# CC2530_PCB_Updated_Antenna_Stim_EMG.net
KiCad netlist of a schematic drawn in EAGLE
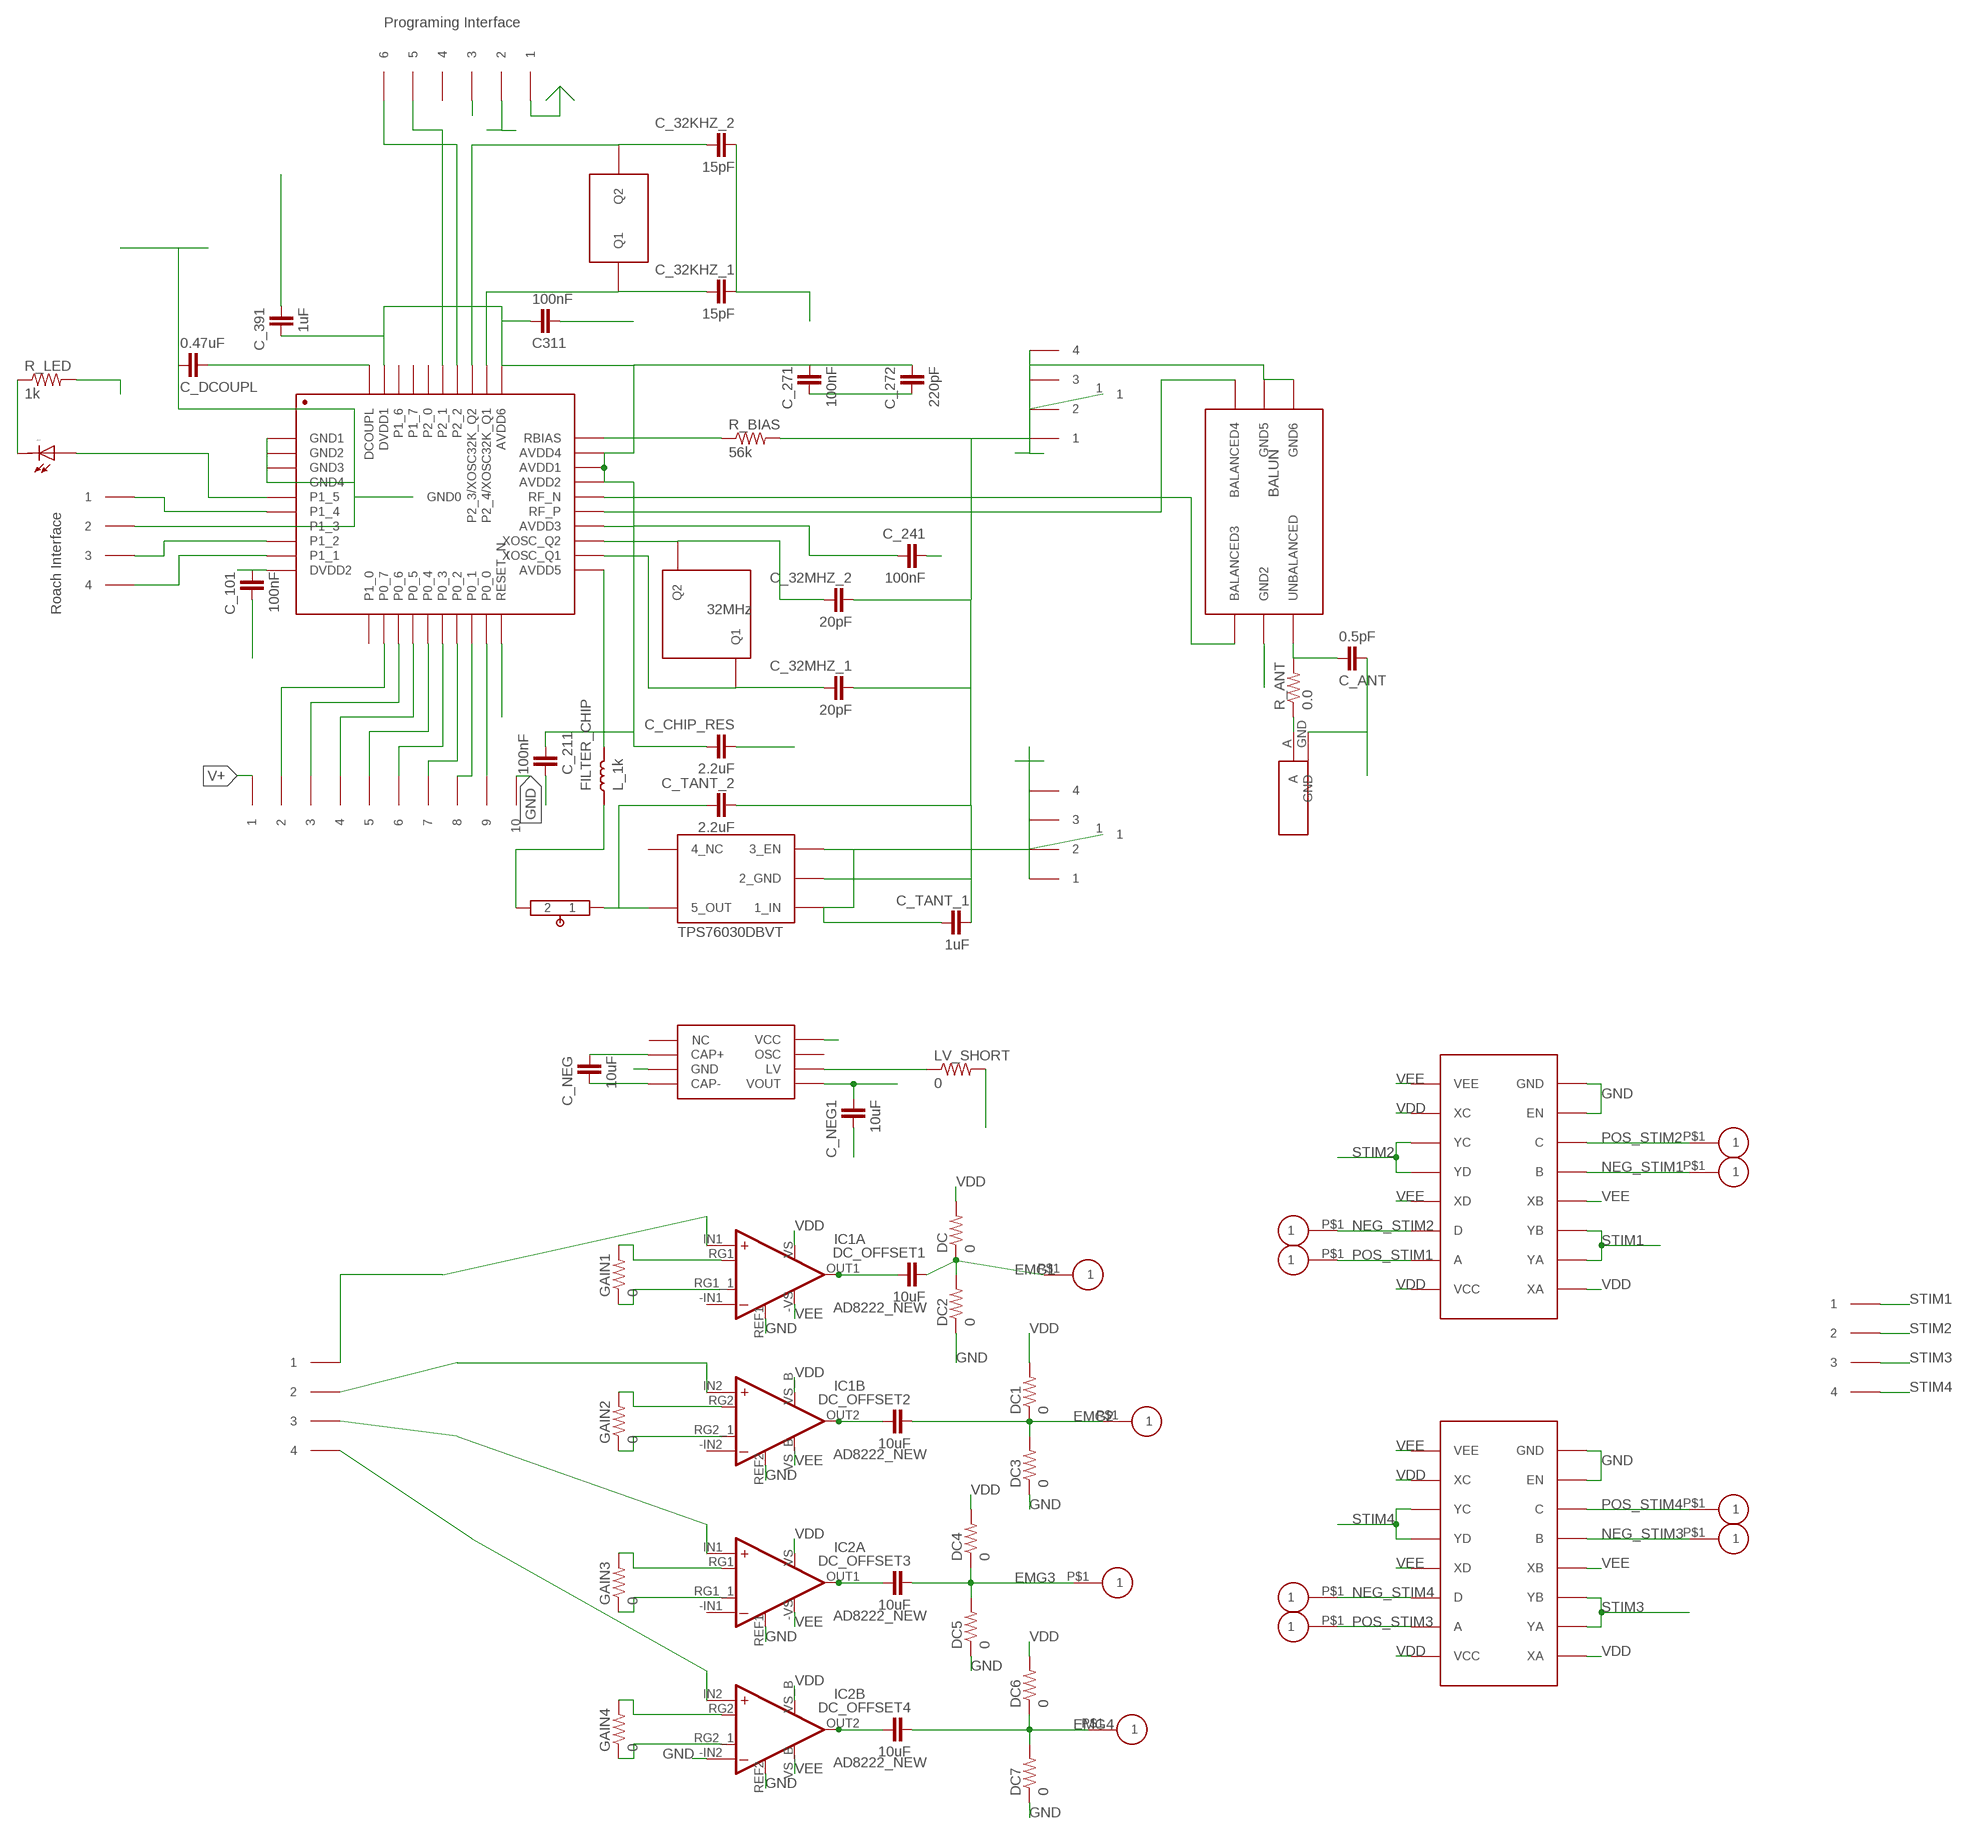
[diagram p0: schematic, sheet 1]

(export (version "E")
  (design (tool "Eeschema 10.0.6"))
  (components
    (comp (ref "32KHZ")
      (value "X32.768KHZ")
      (footprint "eagle-import:X32.768KHZ")
      (libsource (lib "eagle-import") (part "X32.768KHZ"))
    )
    (comp (ref "C311")
      (value "100nF")
      (footprint "eagle-import:0201_R_L_C")
      (libsource (lib "eagle-import") (part "0Y0X_C0201"))
    )
    (comp (ref "C_32KHZ_1")
      (value "15pF")
      (footprint "eagle-import:0201_R_L_C")
      (libsource (lib "eagle-import") (part "0Y0X_C0201"))
    )
    (comp (ref "C_32KHZ_2")
      (value "15pF")
      (footprint "eagle-import:0201_R_L_C")
      (libsource (lib "eagle-import") (part "0Y0X_C0201"))
    )
    (comp (ref "C_32MHZ_1")
      (value "20pF")
      (footprint "eagle-import:0201_R_L_C")
      (libsource (lib "eagle-import") (part "0Y0X_C0201"))
    )
    (comp (ref "C_32MHZ_2")
      (value "20pF")
      (footprint "eagle-import:0201_R_L_C")
      (libsource (lib "eagle-import") (part "0Y0X_C0201"))
    )
    (comp (ref "C_101")
      (value "100nF")
      (footprint "eagle-import:0201_R_L_C")
      (libsource (lib "eagle-import") (part "0Y0X_C0201"))
    )
    (comp (ref "C_211")
      (value "100nF")
      (footprint "eagle-import:0201_R_L_C")
      (libsource (lib "eagle-import") (part "0Y0X_C0201"))
    )
    (comp (ref "C_241")
      (value "100nF")
      (footprint "eagle-import:0201_R_L_C")
      (libsource (lib "eagle-import") (part "0Y0X_C0201"))
    )
    (comp (ref "C_271")
      (value "100nF")
      (footprint "eagle-import:0201_R_L_C")
      (libsource (lib "eagle-import") (part "0Y0X_C0201"))
    )
    (comp (ref "C_272")
      (value "220pF")
      (footprint "eagle-import:0201_R_L_C")
      (libsource (lib "eagle-import") (part "0Y0X_C0201"))
    )
    (comp (ref "C_391")
      (value "1uF")
      (footprint "eagle-import:0201_R_L_C")
      (libsource (lib "eagle-import") (part "0Y0X_C0201"))
    )
    (comp (ref "C_ANT")
      (value "0.5pF")
      (footprint "eagle-import:0201_R_L_C")
      (libsource (lib "eagle-import") (part "0Y0X_C0201"))
    )
    (comp (ref "C_CHIP_RES")
      (value "2.2uF")
      (footprint "eagle-import:0402_R_L_C")
      (libsource (lib "eagle-import") (part "0Y0X_C0402"))
    )
    (comp (ref "C_DCOUPL")
      (value "0.47uF")
      (footprint "eagle-import:0201_R_L_C")
      (libsource (lib "eagle-import") (part "0Y0X_C0201"))
    )
    (comp (ref "C_NEG")
      (value "10uF")
      (footprint "eagle-import:0402_R_L_C")
      (libsource (lib "eagle-import") (part "0Y0X_C0402"))
    )
    (comp (ref "C_NEG1")
      (value "10uF")
      (footprint "eagle-import:0402_R_L_C")
      (libsource (lib "eagle-import") (part "0Y0X_C0402"))
    )
    (comp (ref "C_TANT_1")
      (value "1uF")
      (footprint "eagle-import:0603_R_L_C")
      (libsource (lib "eagle-import") (part "0Y0X_C0603"))
    )
    (comp (ref "C_TANT_2")
      (value "2.2uF")
      (footprint "eagle-import:0603_R_L_C")
      (libsource (lib "eagle-import") (part "0Y0X_C0603"))
    )
    (comp (ref "DC")
      (value "0")
      (footprint "eagle-import:0402_R_L_C")
      (libsource (lib "eagle-import") (part "0Y0X_R0402"))
    )
    (comp (ref "DC1")
      (value "0")
      (footprint "eagle-import:0402_R_L_C")
      (libsource (lib "eagle-import") (part "0Y0X_R0402"))
    )
    (comp (ref "DC2")
      (value "0")
      (footprint "eagle-import:0402_R_L_C")
      (libsource (lib "eagle-import") (part "0Y0X_R0402"))
    )
    (comp (ref "DC3")
      (value "0")
      (footprint "eagle-import:0402_R_L_C")
      (libsource (lib "eagle-import") (part "0Y0X_R0402"))
    )
    (comp (ref "DC4")
      (value "0")
      (footprint "eagle-import:0402_R_L_C")
      (libsource (lib "eagle-import") (part "0Y0X_R0402"))
    )
    (comp (ref "DC5")
      (value "0")
      (footprint "eagle-import:0402_R_L_C")
      (libsource (lib "eagle-import") (part "0Y0X_R0402"))
    )
    (comp (ref "DC6")
      (value "0")
      (footprint "eagle-import:0402_R_L_C")
      (libsource (lib "eagle-import") (part "0Y0X_R0402"))
    )
    (comp (ref "DC7")
      (value "0")
      (footprint "eagle-import:0402_R_L_C")
      (libsource (lib "eagle-import") (part "0Y0X_R0402"))
    )
    (comp (ref "DC_OFFSET1")
      (value "10uF")
      (footprint "eagle-import:0402_R_L_C")
      (libsource (lib "eagle-import") (part "0Y0X_C0402"))
    )
    (comp (ref "DC_OFFSET2")
      (value "10uF")
      (footprint "eagle-import:0402_R_L_C")
      (libsource (lib "eagle-import") (part "0Y0X_C0402"))
    )
    (comp (ref "DC_OFFSET3")
      (value "10uF")
      (footprint "eagle-import:0402_R_L_C")
      (libsource (lib "eagle-import") (part "0Y0X_C0402"))
    )
    (comp (ref "DC_OFFSET4")
      (value "10uF")
      (footprint "eagle-import:0402_R_L_C")
      (libsource (lib "eagle-import") (part "0Y0X_C0402"))
    )
    (comp (ref "EMG1")
      (value "DBG_ELECTRODE")
      (footprint "eagle-import:DBG_ELECTRODE")
      (libsource (lib "eagle-import") (part "DBG_ELECTRODE"))
    )
    (comp (ref "FILTER_CHIP")
      (value "L_1k")
      (footprint "eagle-import:0402_R_L_C")
      (libsource (lib "eagle-import") (part "0Y0X_L0402"))
    )
    (comp (ref "GAIN1")
      (value "0")
      (footprint "eagle-import:0402_R_L_C")
      (libsource (lib "eagle-import") (part "0Y0X_R0402"))
    )
    (comp (ref "GAIN2")
      (value "0")
      (footprint "eagle-import:0402_R_L_C")
      (libsource (lib "eagle-import") (part "0Y0X_R0402"))
    )
    (comp (ref "GAIN3")
      (value "0")
      (footprint "eagle-import:0402_R_L_C")
      (libsource (lib "eagle-import") (part "0Y0X_R0402"))
    )
    (comp (ref "GAIN4")
      (value "0")
      (footprint "eagle-import:0402_R_L_C")
      (libsource (lib "eagle-import") (part "0Y0X_R0402"))
    )
    (comp (ref "GND_IN")
      (value "FFC4POS")
      (footprint "eagle-import:FFC4POS")
      (libsource (lib "eagle-import") (part "FFC4POS"))
    )
    (comp (ref "IC1")
      (value "AD8222_NEW")
      (footprint "eagle-import:QFN-16")
      (libsource (lib "eagle-import") (part "AD8222_NEW"))
    )
    (comp (ref "IC2")
      (value "AD8222_NEW")
      (footprint "eagle-import:QFN-16")
      (libsource (lib "eagle-import") (part "AD8222_NEW"))
    )
    (comp (ref "INVERTED_F-ANTENNA")
      (value "ANTENNA")
      (footprint "eagle-import:ANTENNA")
      (libsource (lib "eagle-import") (part "ANTENNA"))
    )
    (comp (ref "LED")
      (value "LED0603")
      (footprint "eagle-import:0603_R_L_C")
      (libsource (lib "eagle-import") (part "LED0603"))
    )
    (comp (ref "LV_SHORT")
      (value "0")
      (footprint "eagle-import:0402_R_L_C")
      (libsource (lib "eagle-import") (part "0Y0X_R0402"))
    )
    (comp (ref "R_ANT")
      (value "0.0")
      (footprint "eagle-import:0201_R_L_C")
      (libsource (lib "eagle-import") (part "0Y0X_R0201"))
    )
    (comp (ref "R_BIAS")
      (value "56k")
      (footprint "eagle-import:0201_R_L_C")
      (libsource (lib "eagle-import") (part "0Y0X_R0201"))
    )
    (comp (ref "R_LED")
      (value "1k")
      (footprint "eagle-import:0402_R_L_C")
      (libsource (lib "eagle-import") (part "0Y0X_R0402"))
    )
    (comp (ref "U$1")
      (value "CC2530")
      (footprint "eagle-import:CC2530")
      (libsource (lib "eagle-import") (part "CC2530"))
    )
    (comp (ref "U$2")
      (value "BALUN")
      (footprint "eagle-import:BALUN")
      (libsource (lib "eagle-import") (part "BALUN"))
    )
    (comp (ref "U$3")
      (value "X32MHZ")
      (footprint "eagle-import:X32MHZ")
      (fields (field (name "X") "32MHz"))
      (libsource (lib "eagle-import") (part "X32MHZ"))
    )
    (comp (ref "U$4")
      (value "TL7660")
      (footprint "eagle-import:S-PDSO-G8")
      (libsource (lib "eagle-import") (part "TL7660"))
    )
    (comp (ref "U$5")
      (value "MC74HC4316A")
      (footprint "eagle-import:SOIC-16-ON-SEMI")
      (libsource (lib "eagle-import") (part "MC74HC4316A"))
    )
    (comp (ref "U$6")
      (value "MC74HC4316A")
      (footprint "eagle-import:SOIC-16-ON-SEMI")
      (libsource (lib "eagle-import") (part "MC74HC4316A"))
    )
    (comp (ref "U$9")
      (value "DBG_ELECTRODE")
      (footprint "eagle-import:DBG_ELECTRODE")
      (libsource (lib "eagle-import") (part "DBG_ELECTRODE"))
    )
    (comp (ref "U$10")
      (value "REGULATOR")
      (footprint "eagle-import:REGULATOR")
      (libsource (lib "eagle-import") (part "REGULATOR"))
    )
    (comp (ref "U$11")
      (value "DBG_ELECTRODE")
      (footprint "eagle-import:DBG_ELECTRODE")
      (libsource (lib "eagle-import") (part "DBG_ELECTRODE"))
    )
    (comp (ref "U$12")
      (value "DBG_ELECTRODE")
      (footprint "eagle-import:DBG_ELECTRODE")
      (libsource (lib "eagle-import") (part "DBG_ELECTRODE"))
    )
    (comp (ref "U$13")
      (value "FFC4POS")
      (footprint "eagle-import:FFC4POS")
      (libsource (lib "eagle-import") (part "FFC4POS"))
    )
    (comp (ref "U$14")
      (value "DBG_ELECTRODE")
      (footprint "eagle-import:DBG_ELECTRODE")
      (libsource (lib "eagle-import") (part "DBG_ELECTRODE"))
    )
    (comp (ref "U$15")
      (value "FFC10POS")
      (footprint "eagle-import:FFC10POS")
      (libsource (lib "eagle-import") (part "FFC10POS"))
    )
    (comp (ref "U$16")
      (value "DBG_ELECTRODE")
      (footprint "eagle-import:DBG_ELECTRODE")
      (libsource (lib "eagle-import") (part "DBG_ELECTRODE"))
    )
    (comp (ref "U$17")
      (value "FFC6POS")
      (footprint "eagle-import:FFC6POS")
      (libsource (lib "eagle-import") (part "FFC6POS"))
    )
    (comp (ref "U$18")
      (value "SWITCH_MANUAL")
      (footprint "eagle-import:SWITCH_MANUAL")
      (libsource (lib "eagle-import") (part "SWITCH_MANUAL"))
    )
    (comp (ref "U$19")
      (value "DBG_ELECTRODE")
      (footprint "eagle-import:DBG_ELECTRODE")
      (libsource (lib "eagle-import") (part "DBG_ELECTRODE"))
    )
    (comp (ref "U$22")
      (value "DBG_ELECTRODE")
      (footprint "eagle-import:DBG_ELECTRODE")
      (libsource (lib "eagle-import") (part "DBG_ELECTRODE"))
    )
    (comp (ref "U$23")
      (value "DBG_ELECTRODE")
      (footprint "eagle-import:DBG_ELECTRODE")
      (libsource (lib "eagle-import") (part "DBG_ELECTRODE"))
    )
    (comp (ref "U$24")
      (value "FFC4POS")
      (footprint "eagle-import:FFC4POS")
      (libsource (lib "eagle-import") (part "FFC4POS"))
    )
    (comp (ref "U$25")
      (value "DBG_ELECTRODE")
      (footprint "eagle-import:DBG_ELECTRODE")
      (libsource (lib "eagle-import") (part "DBG_ELECTRODE"))
    )
    (comp (ref "U$26")
      (value "DBG_ELECTRODE")
      (footprint "eagle-import:DBG_ELECTRODE")
      (libsource (lib "eagle-import") (part "DBG_ELECTRODE"))
    )
    (comp (ref "U$27")
      (value "DBG_ELECTRODE")
      (footprint "eagle-import:DBG_ELECTRODE")
      (libsource (lib "eagle-import") (part "DBG_ELECTRODE"))
    )
    (comp (ref "U$28")
      (value "FFC4POS")
      (footprint "eagle-import:FFC4POS")
      (libsource (lib "eagle-import") (part "FFC4POS"))
    )
    (comp (ref "V+_IN")
      (value "FFC4POS")
      (footprint "eagle-import:FFC4POS")
      (libsource (lib "eagle-import") (part "FFC4POS"))
    )
    (comp (ref "WIRE+")
      (value "DRILL_CONNECT")
      (footprint "eagle-import:DRILL_CONNECT")
      (libsource (lib "eagle-import") (part "DRILL_CONNECT"))
    )
    (comp (ref "WIRE-")
      (value "DRILL_CONNECT")
      (footprint "eagle-import:DRILL_CONNECT")
      (libsource (lib "eagle-import") (part "DRILL_CONNECT"))
    )
  )
  (nets
    (net (code "1") (name "/EMG1") (class "Default")
      (node (ref "DC") (pin "1") (pinfunction "1_1") (pintype "passive"))
      (node (ref "DC2") (pin "2") (pinfunction "2_2") (pintype "passive"))
      (node (ref "DC_OFFSET1") (pin "2") (pinfunction "2_2") (pintype "passive"))
      (node (ref "EMG1") (pin "P$1") (pinfunction "1_P$1") (pintype "bidirectional"))
    )
    (net (code "2") (name "/EMG2") (class "Default")
      (node (ref "DC1") (pin "1") (pinfunction "1_1") (pintype "passive"))
      (node (ref "DC3") (pin "2") (pinfunction "2_2") (pintype "passive"))
      (node (ref "DC_OFFSET2") (pin "2") (pinfunction "2_2") (pintype "passive"))
      (node (ref "U$25") (pin "P$1") (pinfunction "1_P$1") (pintype "bidirectional"))
    )
    (net (code "3") (name "/EMG3") (class "Default")
      (node (ref "DC4") (pin "1") (pinfunction "1_1") (pintype "passive"))
      (node (ref "DC5") (pin "2") (pinfunction "2_2") (pintype "passive"))
      (node (ref "DC_OFFSET3") (pin "2") (pinfunction "2_2") (pintype "passive"))
      (node (ref "U$26") (pin "P$1") (pinfunction "1_P$1") (pintype "bidirectional"))
    )
    (net (code "4") (name "/EMG4") (class "Default")
      (node (ref "DC6") (pin "1") (pinfunction "1_1") (pintype "passive"))
      (node (ref "DC7") (pin "2") (pinfunction "2_2") (pintype "passive"))
      (node (ref "DC_OFFSET4") (pin "2") (pinfunction "2_2") (pintype "passive"))
      (node (ref "U$27") (pin "P$1") (pinfunction "1_P$1") (pintype "bidirectional"))
    )
    (net (code "5") (name "/NC") (class "Default")
      (node (ref "U$4") (pin "1") (pinfunction "NC_1") (pintype "power_in"))
    )
    (net (code "6") (name "/NEG_STIM1") (class "Default")
      (node (ref "U$14") (pin "P$1") (pinfunction "1_P$1") (pintype "bidirectional"))
      (node (ref "U$5") (pin "5") (pinfunction "B_5") (pintype "input"))
    )
    (net (code "7") (name "/NEG_STIM2") (class "Default")
      (node (ref "U$5") (pin "14") (pinfunction "D_14") (pintype "input"))
      (node (ref "U$9") (pin "P$1") (pinfunction "1_P$1") (pintype "bidirectional"))
    )
    (net (code "8") (name "/NEG_STIM3") (class "Default")
      (node (ref "U$19") (pin "P$1") (pinfunction "1_P$1") (pintype "bidirectional"))
      (node (ref "U$6") (pin "5") (pinfunction "B_5") (pintype "input"))
    )
    (net (code "9") (name "/NEG_STIM4") (class "Default")
      (node (ref "U$22") (pin "P$1") (pinfunction "1_P$1") (pintype "bidirectional"))
      (node (ref "U$6") (pin "14") (pinfunction "D_14") (pintype "input"))
    )
    (net (code "10") (name "/OSC") (class "Default")
      (node (ref "U$4") (pin "7") (pinfunction "OSC_7") (pintype "power_in"))
    )
    (net (code "11") (name "/POS_STIM1") (class "Default")
      (node (ref "U$11") (pin "P$1") (pinfunction "1_P$1") (pintype "bidirectional"))
      (node (ref "U$5") (pin "15") (pinfunction "A_15") (pintype "input"))
    )
    (net (code "12") (name "/POS_STIM2") (class "Default")
      (node (ref "U$12") (pin "P$1") (pinfunction "1_P$1") (pintype "bidirectional"))
      (node (ref "U$5") (pin "6") (pinfunction "C_6") (pintype "input"))
    )
    (net (code "13") (name "/POS_STIM3") (class "Default")
      (node (ref "U$23") (pin "P$1") (pinfunction "1_P$1") (pintype "bidirectional"))
      (node (ref "U$6") (pin "15") (pinfunction "A_15") (pintype "input"))
    )
    (net (code "14") (name "/POS_STIM4") (class "Default")
      (node (ref "U$16") (pin "P$1") (pinfunction "1_P$1") (pintype "bidirectional"))
      (node (ref "U$6") (pin "6") (pinfunction "C_6") (pintype "input"))
    )
    (net (code "15") (name "/RESET") (class "Default")
      (node (ref "U$1") (pin "RESET_N") (pinfunction "RESET_N_RESET_N") (pintype "input"))
      (node (ref "U$17") (pin "3") (pinfunction "3_3") (pintype "bidirectional"))
    )
    (net (code "16") (name "/STIM1") (class "Default")
      (node (ref "U$28") (pin "1") (pinfunction "1_1") (pintype "bidirectional"))
      (node (ref "U$5") (pin "2") (pinfunction "YA_2") (pintype "output"))
      (node (ref "U$5") (pin "3") (pinfunction "YB_3") (pintype "output"))
    )
    (net (code "17") (name "/STIM2") (class "Default")
      (node (ref "U$28") (pin "2") (pinfunction "2_2") (pintype "bidirectional"))
      (node (ref "U$5") (pin "11") (pinfunction "YC_11") (pintype "output"))
      (node (ref "U$5") (pin "12") (pinfunction "YD_12") (pintype "output"))
    )
    (net (code "18") (name "/STIM3") (class "Default")
      (node (ref "U$28") (pin "3") (pinfunction "3_3") (pintype "bidirectional"))
      (node (ref "U$6") (pin "2") (pinfunction "YA_2") (pintype "output"))
      (node (ref "U$6") (pin "3") (pinfunction "YB_3") (pintype "output"))
    )
    (net (code "19") (name "/STIM4") (class "Default")
      (node (ref "U$28") (pin "4") (pinfunction "4_4") (pintype "bidirectional"))
      (node (ref "U$6") (pin "11") (pinfunction "YC_11") (pintype "output"))
      (node (ref "U$6") (pin "12") (pinfunction "YD_12") (pintype "output"))
    )
    (net (code "20") (name "/VDD") (class "Default")
      (node (ref "C311") (pin "2") (pinfunction "2_2") (pintype "passive"))
      (node (ref "C_101") (pin "2") (pinfunction "2_2") (pintype "passive"))
      (node (ref "C_211") (pin "1") (pinfunction "1_1") (pintype "passive"))
      (node (ref "C_241") (pin "1") (pinfunction "1_1") (pintype "passive"))
      (node (ref "C_271") (pin "2") (pinfunction "2_2") (pintype "passive"))
      (node (ref "C_272") (pin "2") (pinfunction "2_2") (pintype "passive"))
      (node (ref "C_391") (pin "1") (pinfunction "1_1") (pintype "passive"))
      (node (ref "C_CHIP_RES") (pin "1") (pinfunction "1_1") (pintype "passive"))
      (node (ref "DC") (pin "2") (pinfunction "2_2") (pintype "passive"))
      (node (ref "DC1") (pin "2") (pinfunction "2_2") (pintype "passive"))
      (node (ref "DC4") (pin "2") (pinfunction "2_2") (pintype "passive"))
      (node (ref "DC6") (pin "2") (pinfunction "2_2") (pintype "passive"))
      (node (ref "FILTER_CHIP") (pin "2") (pinfunction "2_2") (pintype "bidirectional"))
      (node (ref "IC1") (pin "VS") (pinfunction "V+_VS") (pintype "power_in"))
      (node (ref "IC1") (pin "VS_B") (pinfunction "V+_VS_B") (pintype "power_in"))
      (node (ref "IC2") (pin "VS") (pinfunction "V+_VS") (pintype "power_in"))
      (node (ref "IC2") (pin "VS_B") (pinfunction "V+_VS_B") (pintype "power_in"))
      (node (ref "U$1") (pin "AVDD1") (pinfunction "AVDD1_AVDD1") (pintype "power_in"))
      (node (ref "U$1") (pin "AVDD2") (pinfunction "AVDD2_AVDD2") (pintype "power_in"))
      (node (ref "U$1") (pin "AVDD3") (pinfunction "AVDD3_AVDD3") (pintype "power_in"))
      (node (ref "U$1") (pin "AVDD4") (pinfunction "AVDD4_AVDD4") (pintype "power_in"))
      (node (ref "U$1") (pin "AVDD5") (pinfunction "AVDD5_AVDD5") (pintype "power_in"))
      (node (ref "U$1") (pin "AVDD6") (pinfunction "AVDD6_AVDD6") (pintype "power_in"))
      (node (ref "U$1") (pin "DVDD1") (pinfunction "DVDD1_DVDD1") (pintype "power_in"))
      (node (ref "U$1") (pin "DVDD2") (pinfunction "DVDD2_DVDD2") (pintype "power_in"))
      (node (ref "U$17") (pin "1") (pinfunction "1_1") (pintype "bidirectional"))
      (node (ref "U$4") (pin "8") (pinfunction "VCC_8") (pintype "power_in"))
      (node (ref "U$5") (pin "1") (pinfunction "XA_1") (pintype "input"))
      (node (ref "U$5") (pin "10") (pinfunction "XC_10") (pintype "input"))
      (node (ref "U$5") (pin "16") (pinfunction "VCC_16") (pintype "power_in"))
      (node (ref "U$6") (pin "1") (pinfunction "XA_1") (pintype "input"))
      (node (ref "U$6") (pin "10") (pinfunction "XC_10") (pintype "input"))
      (node (ref "U$6") (pin "16") (pinfunction "VCC_16") (pintype "power_in"))
    )
    (net (code "21") (name "/VEE") (class "Default")
      (node (ref "C_NEG1") (pin "2") (pinfunction "2_2") (pintype "passive"))
      (node (ref "IC1") (pin "-VS") (pinfunction "V-_-VS") (pintype "power_in"))
      (node (ref "IC1") (pin "-VS_B") (pinfunction "V-_-VS_B") (pintype "power_in"))
      (node (ref "IC2") (pin "-VS") (pinfunction "V-_-VS") (pintype "power_in"))
      (node (ref "IC2") (pin "-VS_B") (pinfunction "V-_-VS_B") (pintype "power_in"))
      (node (ref "U$4") (pin "5") (pinfunction "VOUT_5") (pintype "power_in"))
      (node (ref "U$5") (pin "13") (pinfunction "XD_13") (pintype "input"))
      (node (ref "U$5") (pin "4") (pinfunction "XB_4") (pintype "input"))
      (node (ref "U$5") (pin "9") (pinfunction "VEE_9") (pintype "power_in"))
      (node (ref "U$6") (pin "13") (pinfunction "XD_13") (pintype "input"))
      (node (ref "U$6") (pin "4") (pinfunction "XB_4") (pintype "input"))
      (node (ref "U$6") (pin "9") (pinfunction "VEE_9") (pintype "power_in"))
    )
    (net (code "22") (name "GND") (class "Default")
      (node (ref "C311") (pin "1") (pinfunction "1_1") (pintype "passive"))
      (node (ref "C_101") (pin "1") (pinfunction "1_1") (pintype "passive"))
      (node (ref "C_211") (pin "2") (pinfunction "2_2") (pintype "passive"))
      (node (ref "C_241") (pin "2") (pinfunction "2_2") (pintype "passive"))
      (node (ref "C_271") (pin "1") (pinfunction "1_1") (pintype "passive"))
      (node (ref "C_272") (pin "1") (pinfunction "1_1") (pintype "passive"))
      (node (ref "C_32KHZ_1") (pin "2") (pinfunction "2_2") (pintype "passive"))
      (node (ref "C_32KHZ_2") (pin "2") (pinfunction "2_2") (pintype "passive"))
      (node (ref "C_32MHZ_1") (pin "2") (pinfunction "2_2") (pintype "passive"))
      (node (ref "C_32MHZ_2") (pin "2") (pinfunction "2_2") (pintype "passive"))
      (node (ref "C_391") (pin "2") (pinfunction "2_2") (pintype "passive"))
      (node (ref "C_ANT") (pin "1") (pinfunction "1_1") (pintype "passive"))
      (node (ref "C_CHIP_RES") (pin "2") (pinfunction "2_2") (pintype "passive"))
      (node (ref "C_DCOUPL") (pin "2") (pinfunction "2_2") (pintype "passive"))
      (node (ref "C_NEG1") (pin "1") (pinfunction "1_1") (pintype "passive"))
      (node (ref "C_TANT_1") (pin "2") (pinfunction "2_2") (pintype "passive"))
      (node (ref "C_TANT_2") (pin "2") (pinfunction "2_2") (pintype "passive"))
      (node (ref "DC2") (pin "1") (pinfunction "1_1") (pintype "passive"))
      (node (ref "DC3") (pin "1") (pinfunction "1_1") (pintype "passive"))
      (node (ref "DC5") (pin "1") (pinfunction "1_1") (pintype "passive"))
      (node (ref "DC7") (pin "1") (pinfunction "1_1") (pintype "passive"))
      (node (ref "GND_IN") (pin "1") (pinfunction "1_1") (pintype "bidirectional"))
      (node (ref "GND_IN") (pin "2") (pinfunction "2_2") (pintype "bidirectional"))
      (node (ref "GND_IN") (pin "3") (pinfunction "3_3") (pintype "bidirectional"))
      (node (ref "GND_IN") (pin "4") (pinfunction "4_4") (pintype "bidirectional"))
      (node (ref "IC1") (pin "REF1") (pinfunction "REF_REF1") (pintype "input"))
      (node (ref "IC1") (pin "REF2") (pinfunction "REF_REF2") (pintype "input"))
      (node (ref "IC2") (pin "-IN2") (pinfunction "-IN_-IN2") (pintype "input"))
      (node (ref "IC2") (pin "REF1") (pinfunction "REF_REF1") (pintype "input"))
      (node (ref "IC2") (pin "REF2") (pinfunction "REF_REF2") (pintype "input"))
      (node (ref "INVERTED_F-ANTENNA") (pin "GND") (pinfunction "GND_GND") (pintype "power_in"))
      (node (ref "LV_SHORT") (pin "2") (pinfunction "2_2") (pintype "passive"))
      (node (ref "R_BIAS") (pin "2") (pinfunction "2_2") (pintype "passive"))
      (node (ref "R_LED") (pin "2") (pinfunction "2_2") (pintype "passive"))
      (node (ref "U$1") (pin "GND0") (pinfunction "GND0_GND0") (pintype "power_in"))
      (node (ref "U$1") (pin "GND001") (pinfunction "GND0_GND001") (pintype "power_in"))
      (node (ref "U$1") (pin "GND002") (pinfunction "GND0_GND002") (pintype "power_in"))
      (node (ref "U$1") (pin "GND003") (pinfunction "GND0_GND003") (pintype "power_in"))
      (node (ref "U$1") (pin "GND004") (pinfunction "GND0_GND004") (pintype "power_in"))
      (node (ref "U$1") (pin "GND005") (pinfunction "GND0_GND005") (pintype "power_in"))
      (node (ref "U$1") (pin "GND006") (pinfunction "GND0_GND006") (pintype "power_in"))
      (node (ref "U$1") (pin "GND007") (pinfunction "GND0_GND007") (pintype "power_in"))
      (node (ref "U$1") (pin "GND008") (pinfunction "GND0_GND008") (pintype "power_in"))
      (node (ref "U$1") (pin "GND009") (pinfunction "GND0_GND009") (pintype "power_in"))
      (node (ref "U$1") (pin "GND010") (pinfunction "GND0_GND010") (pintype "power_in"))
      (node (ref "U$1") (pin "GND011") (pinfunction "GND0_GND011") (pintype "power_in"))
      (node (ref "U$1") (pin "GND012") (pinfunction "GND0_GND012") (pintype "power_in"))
      (node (ref "U$1") (pin "GND013") (pinfunction "GND0_GND013") (pintype "power_in"))
      (node (ref "U$1") (pin "GND014") (pinfunction "GND0_GND014") (pintype "power_in"))
      (node (ref "U$1") (pin "GND015") (pinfunction "GND0_GND015") (pintype "power_in"))
      (node (ref "U$1") (pin "GND016") (pinfunction "GND0_GND016") (pintype "power_in"))
      (node (ref "U$1") (pin "GND1") (pinfunction "GND1_GND1") (pintype "power_in"))
      (node (ref "U$1") (pin "GND2") (pinfunction "GND2_GND2") (pintype "power_in"))
      (node (ref "U$1") (pin "GND3") (pinfunction "GND3_GND3") (pintype "power_in"))
      (node (ref "U$1") (pin "GND4") (pinfunction "GND4_GND4") (pintype "power_in"))
      (node (ref "U$1") (pin "P1_3") (pinfunction "P1_3_P1_3") (pintype "bidirectional"))
      (node (ref "U$10") (pin "2") (pinfunction "2_GND_2") (pintype "power_in"))
      (node (ref "U$13") (pin "2") (pinfunction "2_2") (pintype "bidirectional"))
      (node (ref "U$15") (pin "10") (pinfunction "10_10") (pintype "bidirectional"))
      (node (ref "U$17") (pin "2") (pinfunction "2_2") (pintype "bidirectional"))
      (node (ref "U$2") (pin "GND2") (pinfunction "GND2_GND2") (pintype "power_in"))
      (node (ref "U$2") (pin "GND5") (pinfunction "GND5_GND5") (pintype "power_in"))
      (node (ref "U$2") (pin "GND6") (pinfunction "GND6_GND6") (pintype "power_in"))
      (node (ref "U$4") (pin "3") (pinfunction "GND_3") (pintype "power_in"))
      (node (ref "U$5") (pin "7") (pinfunction "EN_7") (pintype "input"))
      (node (ref "U$5") (pin "8") (pinfunction "GND_8") (pintype "power_in"))
      (node (ref "U$6") (pin "7") (pinfunction "EN_7") (pintype "input"))
      (node (ref "U$6") (pin "8") (pinfunction "GND_8") (pintype "power_in"))
      (node (ref "WIRE-") (pin "1") (pinfunction "1_1") (pintype "bidirectional"))
    )
    (net (code "23") (name "Net-(32KHZ-PadQ1)") (class "Default")
      (node (ref "32KHZ") (pin "Q1") (pinfunction "Q1_Q1") (pintype "bidirectional"))
      (node (ref "C_32KHZ_1") (pin "1") (pinfunction "1_1") (pintype "passive"))
      (node (ref "U$1") (pin "P2_4/XOSC32K_Q1") (pinfunction "P2_4/XOSC32K_Q1_P2_4/XOSC32K_Q1") (pintype "bidirectional"))
    )
    (net (code "24") (name "Net-(32KHZ-PadQ2)") (class "Default")
      (node (ref "32KHZ") (pin "Q2") (pinfunction "Q2_Q2") (pintype "bidirectional"))
      (node (ref "C_32KHZ_2") (pin "1") (pinfunction "1_1") (pintype "passive"))
      (node (ref "U$1") (pin "P2_3/XOSC32K_Q2") (pinfunction "P2_3/XOSC32K_Q2_P2_3/XOSC32K_Q2") (pintype "bidirectional"))
    )
    (net (code "25") (name "Net-(C_32MHZ_1-Pad1)") (class "Default")
      (node (ref "C_32MHZ_1") (pin "1") (pinfunction "1_1") (pintype "passive"))
      (node (ref "U$1") (pin "XOSC_Q1") (pinfunction "XOSC_Q1_XOSC_Q1") (pintype "bidirectional"))
      (node (ref "U$3") (pin "Q1") (pinfunction "Q1_Q1") (pintype "bidirectional"))
    )
    (net (code "26") (name "Net-(C_32MHZ_2-Pad1)") (class "Default")
      (node (ref "C_32MHZ_2") (pin "1") (pinfunction "1_1") (pintype "passive"))
      (node (ref "U$1") (pin "XOSC_Q2") (pinfunction "XOSC_Q2_XOSC_Q2") (pintype "bidirectional"))
      (node (ref "U$3") (pin "Q2") (pinfunction "Q2_Q2") (pintype "bidirectional"))
    )
    (net (code "27") (name "Net-(C_ANT-Pad2)") (class "Default")
      (node (ref "C_ANT") (pin "2") (pinfunction "2_2") (pintype "passive"))
      (node (ref "R_ANT") (pin "2") (pinfunction "2_2") (pintype "passive"))
      (node (ref "U$2") (pin "UNBALANCED") (pinfunction "UNBALANCED_UNBALANCED") (pintype "bidirectional"))
    )
    (net (code "28") (name "Net-(C_DCOUPL-Pad1)") (class "Default")
      (node (ref "C_DCOUPL") (pin "1") (pinfunction "1_1") (pintype "passive"))
      (node (ref "U$1") (pin "DCOUPL") (pinfunction "DCOUPL_DCOUPL") (pintype "power_in"))
    )
    (net (code "29") (name "Net-(FILTER_CHIP-Pad1)") (class "Default")
      (node (ref "FILTER_CHIP") (pin "1") (pinfunction "1_1") (pintype "bidirectional"))
      (node (ref "U$18") (pin "2") (pinfunction "2_2") (pintype "bidirectional"))
    )
    (net (code "30") (name "Net-(GAIN1-Pad1)") (class "Default")
      (node (ref "GAIN1") (pin "1") (pinfunction "1_1") (pintype "passive"))
      (node (ref "IC1") (pin "RG1_1") (pinfunction "RG1_1_RG1_1") (pintype "input"))
    )
    (net (code "31") (name "Net-(GAIN1-Pad2)") (class "Default")
      (node (ref "GAIN1") (pin "2") (pinfunction "2_2") (pintype "passive"))
      (node (ref "IC1") (pin "RG1") (pinfunction "RG1_RG1") (pintype "input"))
    )
    (net (code "32") (name "Net-(GAIN3-Pad1)") (class "Default")
      (node (ref "GAIN3") (pin "1") (pinfunction "1_1") (pintype "passive"))
      (node (ref "IC2") (pin "RG1_1") (pinfunction "RG1_1_RG1_1") (pintype "input"))
    )
    (net (code "33") (name "Net-(GAIN3-Pad2)") (class "Default")
      (node (ref "GAIN3") (pin "2") (pinfunction "2_2") (pintype "passive"))
      (node (ref "IC2") (pin "RG1") (pinfunction "RG1_RG1") (pintype "input"))
    )
    (net (code "34") (name "Net-(IC1A-+IN)") (class "Default")
      (node (ref "IC1") (pin "IN1") (pinfunction "+IN_IN1") (pintype "input"))
      (node (ref "U$24") (pin "1") (pinfunction "1_1") (pintype "bidirectional"))
    )
    (net (code "35") (name "Net-(IC1A-OUT)") (class "Default")
      (node (ref "DC_OFFSET1") (pin "1") (pinfunction "1_1") (pintype "passive"))
      (node (ref "IC1") (pin "OUT1") (pinfunction "OUT_OUT1") (pintype "input"))
    )
    (net (code "36") (name "Net-(IC1B-+IN)") (class "Default")
      (node (ref "IC1") (pin "IN2") (pinfunction "+IN_IN2") (pintype "input"))
      (node (ref "U$24") (pin "2") (pinfunction "2_2") (pintype "bidirectional"))
    )
    (net (code "37") (name "Net-(IC1B-OUT)") (class "Default")
      (node (ref "DC_OFFSET2") (pin "1") (pinfunction "1_1") (pintype "passive"))
      (node (ref "IC1") (pin "OUT2") (pinfunction "OUT_OUT2") (pintype "input"))
    )
    (net (code "38") (name "Net-(IC1B-RG1)") (class "Default")
      (node (ref "GAIN2") (pin "2") (pinfunction "2_2") (pintype "passive"))
      (node (ref "IC1") (pin "RG2") (pinfunction "RG1_RG2") (pintype "input"))
    )
    (net (code "39") (name "Net-(IC1B-RG1_1)") (class "Default")
      (node (ref "GAIN2") (pin "1") (pinfunction "1_1") (pintype "passive"))
      (node (ref "IC1") (pin "RG2_1") (pinfunction "RG1_1_RG2_1") (pintype "input"))
    )
    (net (code "40") (name "Net-(IC2A-+IN)") (class "Default")
      (node (ref "IC2") (pin "IN1") (pinfunction "+IN_IN1") (pintype "input"))
      (node (ref "U$24") (pin "3") (pinfunction "3_3") (pintype "bidirectional"))
    )
    (net (code "41") (name "Net-(IC2A-OUT)") (class "Default")
      (node (ref "DC_OFFSET3") (pin "1") (pinfunction "1_1") (pintype "passive"))
      (node (ref "IC2") (pin "OUT1") (pinfunction "OUT_OUT1") (pintype "input"))
    )
    (net (code "42") (name "Net-(IC2B-+IN)") (class "Default")
      (node (ref "IC2") (pin "IN2") (pinfunction "+IN_IN2") (pintype "input"))
      (node (ref "U$24") (pin "4") (pinfunction "4_4") (pintype "bidirectional"))
    )
    (net (code "43") (name "Net-(IC2B-OUT)") (class "Default")
      (node (ref "DC_OFFSET4") (pin "1") (pinfunction "1_1") (pintype "passive"))
      (node (ref "IC2") (pin "OUT2") (pinfunction "OUT_OUT2") (pintype "input"))
    )
    (net (code "44") (name "Net-(IC2B-RG1)") (class "Default")
      (node (ref "GAIN4") (pin "2") (pinfunction "2_2") (pintype "passive"))
      (node (ref "IC2") (pin "RG2") (pinfunction "RG1_RG2") (pintype "input"))
    )
    (net (code "45") (name "Net-(IC2B-RG1_1)") (class "Default")
      (node (ref "GAIN4") (pin "1") (pinfunction "1_1") (pintype "passive"))
      (node (ref "IC2") (pin "RG2_1") (pinfunction "RG1_1_RG2_1") (pintype "input"))
    )
    (net (code "46") (name "Net-(INVERTED_F-ANTENNA-PadA)") (class "Default")
      (node (ref "INVERTED_F-ANTENNA") (pin "A") (pinfunction "A_A") (pintype "bidirectional"))
      (node (ref "R_ANT") (pin "1") (pinfunction "1_1") (pintype "passive"))
    )
    (net (code "47") (name "Net-(LED-A)") (class "Default")
      (node (ref "LED") (pin "1") (pinfunction "A_1") (pintype "passive"))
      (node (ref "U$1") (pin "P1_5") (pinfunction "P1_5_P1_5") (pintype "bidirectional"))
    )
    (net (code "48") (name "Net-(LED-C)") (class "Default")
      (node (ref "LED") (pin "2") (pinfunction "C_2") (pintype "passive"))
      (node (ref "R_LED") (pin "1") (pinfunction "1_1") (pintype "passive"))
    )
    (net (code "49") (name "Net-(R_BIAS-Pad1)") (class "Default")
      (node (ref "R_BIAS") (pin "1") (pinfunction "1_1") (pintype "passive"))
      (node (ref "U$1") (pin "RBIAS") (pinfunction "RBIAS_RBIAS") (pintype "bidirectional"))
    )
    (net (code "50") (name "Net-(U$1-PadP0_0)") (class "Default")
      (node (ref "U$1") (pin "P0_0") (pinfunction "P0_0_P0_0") (pintype "bidirectional"))
      (node (ref "U$15") (pin "9") (pinfunction "9_9") (pintype "bidirectional"))
    )
    (net (code "51") (name "Net-(U$1-PadP0_1)") (class "Default")
      (node (ref "U$1") (pin "P0_1") (pinfunction "P0_1_P0_1") (pintype "bidirectional"))
      (node (ref "U$15") (pin "8") (pinfunction "8_8") (pintype "bidirectional"))
    )
    (net (code "52") (name "Net-(U$1-PadP0_2)") (class "Default")
      (node (ref "U$1") (pin "P0_2") (pinfunction "P0_2_P0_2") (pintype "bidirectional"))
      (node (ref "U$15") (pin "7") (pinfunction "7_7") (pintype "bidirectional"))
    )
    (net (code "53") (name "Net-(U$1-PadP0_3)") (class "Default")
      (node (ref "U$1") (pin "P0_3") (pinfunction "P0_3_P0_3") (pintype "bidirectional"))
      (node (ref "U$15") (pin "6") (pinfunction "6_6") (pintype "bidirectional"))
    )
    (net (code "54") (name "Net-(U$1-PadP0_4)") (class "Default")
      (node (ref "U$1") (pin "P0_4") (pinfunction "P0_4_P0_4") (pintype "bidirectional"))
      (node (ref "U$15") (pin "5") (pinfunction "5_5") (pintype "bidirectional"))
    )
    (net (code "55") (name "Net-(U$1-PadP0_5)") (class "Default")
      (node (ref "U$1") (pin "P0_5") (pinfunction "P0_5_P0_5") (pintype "bidirectional"))
      (node (ref "U$15") (pin "4") (pinfunction "4_4") (pintype "bidirectional"))
    )
    (net (code "56") (name "Net-(U$1-PadP0_6)") (class "Default")
      (node (ref "U$1") (pin "P0_6") (pinfunction "P0_6_P0_6") (pintype "bidirectional"))
      (node (ref "U$15") (pin "3") (pinfunction "3_3") (pintype "bidirectional"))
    )
    (net (code "57") (name "Net-(U$1-PadP0_7)") (class "Default")
      (node (ref "U$1") (pin "P0_7") (pinfunction "P0_7_P0_7") (pintype "bidirectional"))
      (node (ref "U$15") (pin "2") (pinfunction "2_2") (pintype "bidirectional"))
    )
    (net (code "58") (name "Net-(U$1-PadP1_1)") (class "Default")
      (node (ref "U$1") (pin "P1_1") (pinfunction "P1_1_P1_1") (pintype "bidirectional"))
      (node (ref "U$13") (pin "4") (pinfunction "4_4") (pintype "bidirectional"))
    )
    (net (code "59") (name "Net-(U$1-PadP1_2)") (class "Default")
      (node (ref "U$1") (pin "P1_2") (pinfunction "P1_2_P1_2") (pintype "bidirectional"))
      (node (ref "U$13") (pin "3") (pinfunction "3_3") (pintype "bidirectional"))
    )
    (net (code "60") (name "Net-(U$1-PadP1_4)") (class "Default")
      (node (ref "U$1") (pin "P1_4") (pinfunction "P1_4_P1_4") (pintype "bidirectional"))
      (node (ref "U$13") (pin "1") (pinfunction "1_1") (pintype "bidirectional"))
    )
    (net (code "61") (name "Net-(U$1-PadP2_1)") (class "Default")
      (node (ref "U$1") (pin "P2_1") (pinfunction "P2_1_P2_1") (pintype "bidirectional"))
      (node (ref "U$17") (pin "5") (pinfunction "5_5") (pintype "bidirectional"))
    )
    (net (code "62") (name "Net-(U$1-PadP2_2)") (class "Default")
      (node (ref "U$1") (pin "P2_2") (pinfunction "P2_2_P2_2") (pintype "bidirectional"))
      (node (ref "U$17") (pin "6") (pinfunction "6_6") (pintype "bidirectional"))
    )
    (net (code "63") (name "Net-(U$1-PadRF_N)") (class "Default")
      (node (ref "U$1") (pin "RF_N") (pinfunction "RF_N_RF_N") (pintype "bidirectional"))
      (node (ref "U$2") (pin "BALANCED3") (pinfunction "BALANCED3_BALANCED3") (pintype "bidirectional"))
    )
    (net (code "64") (name "Net-(U$1-PadRF_P)") (class "Default")
      (node (ref "U$1") (pin "RF_P") (pinfunction "RF_P_RF_P") (pintype "bidirectional"))
      (node (ref "U$2") (pin "BALANCED4") (pinfunction "BALANCED4_BALANCED4") (pintype "bidirectional"))
    )
    (net (code "65") (name "Net-(U$4-CAP+)") (class "Default")
      (node (ref "C_NEG") (pin "2") (pinfunction "2_2") (pintype "passive"))
      (node (ref "U$4") (pin "2") (pinfunction "CAP+_2") (pintype "power_in"))
    )
    (net (code "66") (name "Net-(U$4-CAP-)") (class "Default")
      (node (ref "C_NEG") (pin "1") (pinfunction "1_1") (pintype "passive"))
      (node (ref "U$4") (pin "4") (pinfunction "CAP-_4") (pintype "power_in"))
    )
    (net (code "67") (name "Net-(U$4-LV)") (class "Default")
      (node (ref "LV_SHORT") (pin "1") (pinfunction "1_1") (pintype "passive"))
      (node (ref "U$4") (pin "6") (pinfunction "LV_6") (pintype "power_in"))
    )
    (net (code "68") (name "Net-(U$10-5_OUT)") (class "Default")
      (node (ref "C_TANT_2") (pin "1") (pinfunction "1_1") (pintype "passive"))
      (node (ref "U$10") (pin "5") (pinfunction "5_OUT_5") (pintype "bidirectional"))
      (node (ref "U$18") (pin "1") (pinfunction "1_1") (pintype "bidirectional"))
    )
    (net (code "69") (name "V+") (class "Default")
      (node (ref "C_TANT_1") (pin "1") (pinfunction "1_1") (pintype "passive"))
      (node (ref "U$10") (pin "1") (pinfunction "1_IN_1") (pintype "bidirectional"))
      (node (ref "U$10") (pin "3") (pinfunction "3_EN_3") (pintype "bidirectional"))
      (node (ref "U$15") (pin "1") (pinfunction "1_1") (pintype "bidirectional"))
      (node (ref "V+_IN") (pin "1") (pinfunction "1_1") (pintype "bidirectional"))
      (node (ref "V+_IN") (pin "2") (pinfunction "2_2") (pintype "bidirectional"))
      (node (ref "V+_IN") (pin "3") (pinfunction "3_3") (pintype "bidirectional"))
      (node (ref "V+_IN") (pin "4") (pinfunction "4_4") (pintype "bidirectional"))
      (node (ref "WIRE+") (pin "1") (pinfunction "1_1") (pintype "bidirectional"))
    )
    (net (code "70") (name "unconnected-(IC1A--IN-Pad-IN1)") (class "Default")
      (node (ref "IC1") (pin "-IN1") (pinfunction "-IN_-IN1") (pintype "input"))
    )
    (net (code "71") (name "unconnected-(IC1B--IN-Pad-IN2)") (class "Default")
      (node (ref "IC1") (pin "-IN2") (pinfunction "-IN_-IN2") (pintype "input"))
    )
    (net (code "72") (name "unconnected-(IC2A--IN-Pad-IN1)") (class "Default")
      (node (ref "IC2") (pin "-IN1") (pinfunction "-IN_-IN1") (pintype "input"))
    )
    (net (code "73") (name "unconnected-(U$1-PadP1_0)") (class "Default")
      (node (ref "U$1") (pin "P1_0") (pinfunction "P1_0_P1_0") (pintype "bidirectional"))
    )
    (net (code "74") (name "unconnected-(U$1-PadP1_6)") (class "Default")
      (node (ref "U$1") (pin "P1_6") (pinfunction "P1_6_P1_6") (pintype "bidirectional"))
    )
    (net (code "75") (name "unconnected-(U$1-PadP1_7)") (class "Default")
      (node (ref "U$1") (pin "P1_7") (pinfunction "P1_7_P1_7") (pintype "bidirectional"))
    )
    (net (code "76") (name "unconnected-(U$1-PadP2_0)") (class "Default")
      (node (ref "U$1") (pin "P2_0") (pinfunction "P2_0_P2_0") (pintype "bidirectional"))
    )
    (net (code "77") (name "unconnected-(U$10-4_NC-Pad4)") (class "Default")
      (node (ref "U$10") (pin "4") (pinfunction "4_NC_4") (pintype "no_connect"))
    )
    (net (code "78") (name "unconnected-(U$17-Pad4)") (class "Default")
      (node (ref "U$17") (pin "4") (pinfunction "4_4") (pintype "bidirectional"))
    )
  )
)
